# Master.net
KiCad netlist of a schematic drawn in Altium Designer
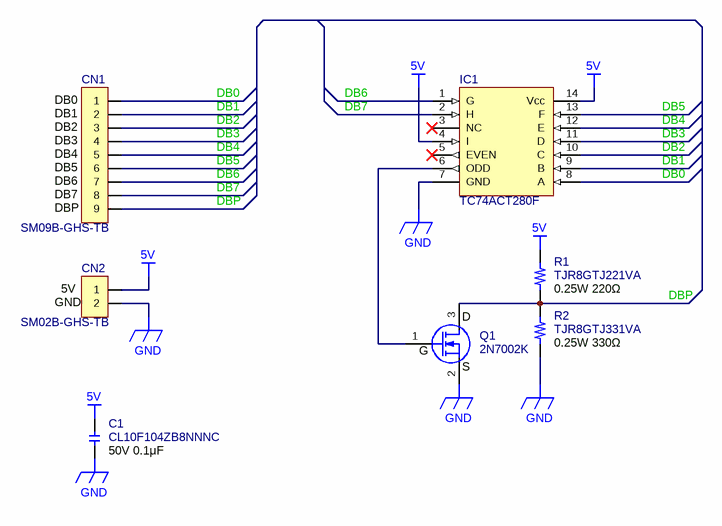
[diagram p0: Master.SchDoc]

(export (version "E")
  (design (tool "Eeschema 10.0.6"))
  (components
    (comp (ref "C1")
      (value "CL10F104ZB8NNNC")
      (footprint "R1608")
      (description "ﾁｯﾌﾟ形積層ｾﾗﾐｯｸｺﾝﾃﾞﾝｻ_50V/0.1μF")
      (libsource (lib "SMD_CL") (part "CL10F104ZB8NNNC"))
    )
    (comp (ref "CN1")
      (value "SM09B-GHS-TB")
      (footprint "CN_SM09B-GHS-TB")
      (description "GHｺﾈｸﾀ9P ｻｲﾄﾞ型 ﾅﾁｭﾗﾙ")
      (libsource (lib "SMD_GH_CONNECTOR") (part "SM09B-GHS-TB"))
    )
    (comp (ref "CN2")
      (value "SM02B-GHS-TB")
      (footprint "CN_SM02B-GHS-TB")
      (description "GHｺﾈｸﾀ2P ｻｲﾄﾞ型 ﾅﾁｭﾗﾙ")
      (libsource (lib "SMD_GH_CONNECTOR") (part "SM02B-GHS-TB"))
    )
    (comp (ref "IC1")
      (value "TC74ACT280F")
      (footprint "SOP14-P-300-1.27A")
      (description "9-Bit Parity Generator/Checker")
      (libsource (lib "SMD_IC") (part "TC74ACT280F"))
    )
    (comp (ref "Q1")
      (value "2N7002K")
      (footprint "SOT-23")
      (description "ｼﾘｺﾝNﾁｬﾝﾈﾙ MOS FET 60V 0.3A")
      (libsource (lib "SMD_DTr") (part "2N7002K"))
    )
    (comp (ref "R1")
      (value "TJR8GTJ221VA")
      (footprint "R3216")
      (description "角形厚膜ﾁｯﾌﾟ抵抗器 0.25W/220Ω")
      (libsource (lib "SMD_TATEYAMA_RESISTOR") (part "TJR8GTJ221VA"))
    )
    (comp (ref "R2")
      (value "TJR8GTJ331VA")
      (footprint "R3216")
      (description "角形厚膜ﾁｯﾌﾟ抵抗器 0.25W/330Ω")
      (libsource (lib "SMD_TATEYAMA_RESISTOR") (part "TJR8GTJ331VA"))
    )
  )
  (nets
    (net (code "1") (name "/DB0") (class "Default")
      (node (ref "CN1") (pin "1") (pinfunction "1_1") (pintype "passive"))
      (node (ref "IC1") (pin "8") (pinfunction "A_8") (pintype "input"))
    )
    (net (code "2") (name "/DB1") (class "Default")
      (node (ref "CN1") (pin "2") (pinfunction "2_2") (pintype "passive"))
      (node (ref "IC1") (pin "9") (pinfunction "B_9") (pintype "input"))
    )
    (net (code "3") (name "/DB2") (class "Default")
      (node (ref "CN1") (pin "3") (pinfunction "3_3") (pintype "passive"))
      (node (ref "IC1") (pin "10") (pinfunction "C_10") (pintype "input"))
    )
    (net (code "4") (name "/DB3") (class "Default")
      (node (ref "CN1") (pin "4") (pinfunction "4_4") (pintype "passive"))
      (node (ref "IC1") (pin "11") (pinfunction "D_11") (pintype "input"))
    )
    (net (code "5") (name "/DB4") (class "Default")
      (node (ref "CN1") (pin "5") (pinfunction "5_5") (pintype "passive"))
      (node (ref "IC1") (pin "12") (pinfunction "E_12") (pintype "input"))
    )
    (net (code "6") (name "/DB5") (class "Default")
      (node (ref "CN1") (pin "6") (pinfunction "6_6") (pintype "passive"))
      (node (ref "IC1") (pin "13") (pinfunction "F_13") (pintype "input"))
    )
    (net (code "7") (name "/DB6") (class "Default")
      (node (ref "CN1") (pin "7") (pinfunction "7_7") (pintype "passive"))
      (node (ref "IC1") (pin "1") (pinfunction "G_1") (pintype "input"))
    )
    (net (code "8") (name "/DB7") (class "Default")
      (node (ref "CN1") (pin "8") (pinfunction "8_8") (pintype "passive"))
      (node (ref "IC1") (pin "2") (pinfunction "H_2") (pintype "input"))
    )
    (net (code "9") (name "/DBP") (class "Default")
      (node (ref "CN1") (pin "9") (pinfunction "9_9") (pintype "passive"))
      (node (ref "Q1") (pin "3") (pinfunction "D_3") (pintype "passive"))
      (node (ref "R1") (pin "2") (pinfunction "2_2") (pintype "passive"))
      (node (ref "R2") (pin "1") (pinfunction "1_1") (pintype "passive"))
    )
    (net (code "10") (name "5V") (class "Default")
      (node (ref "C1") (pin "1") (pinfunction "1_1") (pintype "passive"))
      (node (ref "CN2") (pin "1") (pinfunction "1_1") (pintype "passive"))
      (node (ref "IC1") (pin "14") (pinfunction "Vcc_14") (pintype "power_in"))
      (node (ref "IC1") (pin "4") (pinfunction "I_4") (pintype "input"))
      (node (ref "R1") (pin "1") (pinfunction "1_1") (pintype "passive"))
    )
    (net (code "11") (name "GND") (class "Default")
      (node (ref "C1") (pin "2") (pinfunction "2_2") (pintype "passive"))
      (node (ref "CN2") (pin "2") (pinfunction "2_2") (pintype "passive"))
      (node (ref "IC1") (pin "7") (pinfunction "GND_7") (pintype "power_in"))
      (node (ref "Q1") (pin "2") (pinfunction "S_2") (pintype "passive"))
      (node (ref "R2") (pin "2") (pinfunction "2_2") (pintype "passive"))
    )
    (net (code "12") (name "Net-(IC1-ODD)") (class "Default")
      (node (ref "IC1") (pin "6") (pinfunction "ODD_6") (pintype "output"))
      (node (ref "Q1") (pin "1") (pinfunction "G_1") (pintype "passive"))
    )
    (net (code "13") (name "unconnected-(IC1-EVEN-Pad5)") (class "Default")
      (node (ref "IC1") (pin "5") (pinfunction "EVEN_5") (pintype "output+no_connect"))
    )
    (net (code "14") (name "unconnected-(IC1-NC-Pad3)") (class "Default")
      (node (ref "IC1") (pin "3") (pinfunction "NC_3") (pintype "passive+no_connect"))
    )
  )
)
